# encoder_breakout.net
KiCad netlist of a schematic drawn in EAGLE
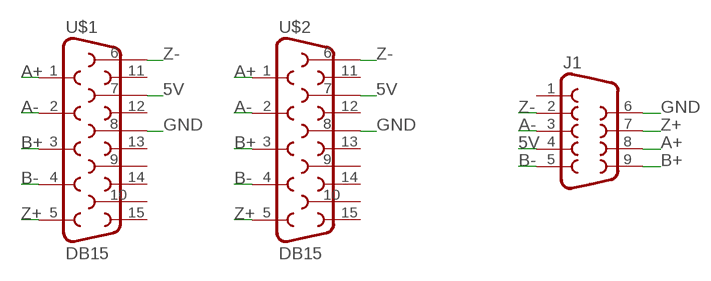
[diagram p0: schematic, sheet 1]

(export (version "E")
  (design (tool "Eeschema 10.0.6"))
  (components
    (comp (ref "J1")
      (value "DB9FEMALE")
      (footprint "eagle-import:DB9")
      (libsource (lib "eagle-import") (part "DB9FEMALE"))
    )
    (comp (ref "U$1")
      (value "DB15")
      (footprint "eagle-import:DB15")
      (libsource (lib "eagle-import") (part "DB15"))
    )
    (comp (ref "U$2")
      (value "DB15")
      (footprint "eagle-import:DB15")
      (libsource (lib "eagle-import") (part "DB15"))
    )
  )
  (nets
    (net (code "1") (name "/5V") (class "Default")
      (node (ref "J1") (pin "4") (pinfunction "4_4") (pintype "passive"))
      (node (ref "U$1") (pin "7") (pinfunction "7_7") (pintype "passive"))
      (node (ref "U$2") (pin "7") (pinfunction "7_7") (pintype "passive"))
    )
    (net (code "2") (name "/A+") (class "Default")
      (node (ref "J1") (pin "8") (pinfunction "8_8") (pintype "passive"))
      (node (ref "U$1") (pin "1") (pinfunction "1_1") (pintype "passive"))
      (node (ref "U$2") (pin "1") (pinfunction "1_1") (pintype "passive"))
    )
    (net (code "3") (name "/A-") (class "Default")
      (node (ref "J1") (pin "3") (pinfunction "3_3") (pintype "passive"))
      (node (ref "U$1") (pin "2") (pinfunction "2_2") (pintype "passive"))
      (node (ref "U$2") (pin "2") (pinfunction "2_2") (pintype "passive"))
    )
    (net (code "4") (name "/B+") (class "Default")
      (node (ref "J1") (pin "9") (pinfunction "9_9") (pintype "passive"))
      (node (ref "U$1") (pin "3") (pinfunction "3_3") (pintype "passive"))
      (node (ref "U$2") (pin "3") (pinfunction "3_3") (pintype "passive"))
    )
    (net (code "5") (name "/B-") (class "Default")
      (node (ref "J1") (pin "5") (pinfunction "5_5") (pintype "passive"))
      (node (ref "U$1") (pin "4") (pinfunction "4_4") (pintype "passive"))
      (node (ref "U$2") (pin "4") (pinfunction "4_4") (pintype "passive"))
    )
    (net (code "6") (name "/GND") (class "Default")
      (node (ref "J1") (pin "6") (pinfunction "6_6") (pintype "passive"))
      (node (ref "U$1") (pin "8") (pinfunction "8_8") (pintype "passive"))
      (node (ref "U$2") (pin "8") (pinfunction "8_8") (pintype "passive"))
    )
    (net (code "7") (name "/Z+") (class "Default")
      (node (ref "J1") (pin "7") (pinfunction "7_7") (pintype "passive"))
      (node (ref "U$1") (pin "5") (pinfunction "5_5") (pintype "passive"))
      (node (ref "U$2") (pin "5") (pinfunction "5_5") (pintype "passive"))
    )
    (net (code "8") (name "/Z-") (class "Default")
      (node (ref "J1") (pin "2") (pinfunction "2_2") (pintype "passive"))
      (node (ref "U$1") (pin "6") (pinfunction "6_6") (pintype "passive"))
      (node (ref "U$2") (pin "6") (pinfunction "6_6") (pintype "passive"))
    )
    (net (code "9") (name "unconnected-(J1-Pad1)") (class "Default")
      (node (ref "J1") (pin "1") (pinfunction "1_1") (pintype "passive"))
    )
    (net (code "10") (name "unconnected-(U$1-Pad9)") (class "Default")
      (node (ref "U$1") (pin "9") (pinfunction "9_9") (pintype "passive"))
    )
    (net (code "11") (name "unconnected-(U$1-Pad10)") (class "Default")
      (node (ref "U$1") (pin "10") (pinfunction "10_10") (pintype "passive"))
    )
    (net (code "12") (name "unconnected-(U$1-Pad11)") (class "Default")
      (node (ref "U$1") (pin "11") (pinfunction "11_11") (pintype "passive"))
    )
    (net (code "13") (name "unconnected-(U$1-Pad12)") (class "Default")
      (node (ref "U$1") (pin "12") (pinfunction "12_12") (pintype "passive"))
    )
    (net (code "14") (name "unconnected-(U$1-Pad13)") (class "Default")
      (node (ref "U$1") (pin "13") (pinfunction "13_13") (pintype "passive"))
    )
    (net (code "15") (name "unconnected-(U$1-Pad14)") (class "Default")
      (node (ref "U$1") (pin "14") (pinfunction "14_14") (pintype "passive"))
    )
    (net (code "16") (name "unconnected-(U$1-Pad15)") (class "Default")
      (node (ref "U$1") (pin "15") (pinfunction "15_15") (pintype "passive"))
    )
    (net (code "17") (name "unconnected-(U$2-Pad9)") (class "Default")
      (node (ref "U$2") (pin "9") (pinfunction "9_9") (pintype "passive"))
    )
    (net (code "18") (name "unconnected-(U$2-Pad10)") (class "Default")
      (node (ref "U$2") (pin "10") (pinfunction "10_10") (pintype "passive"))
    )
    (net (code "19") (name "unconnected-(U$2-Pad11)") (class "Default")
      (node (ref "U$2") (pin "11") (pinfunction "11_11") (pintype "passive"))
    )
    (net (code "20") (name "unconnected-(U$2-Pad12)") (class "Default")
      (node (ref "U$2") (pin "12") (pinfunction "12_12") (pintype "passive"))
    )
    (net (code "21") (name "unconnected-(U$2-Pad13)") (class "Default")
      (node (ref "U$2") (pin "13") (pinfunction "13_13") (pintype "passive"))
    )
    (net (code "22") (name "unconnected-(U$2-Pad14)") (class "Default")
      (node (ref "U$2") (pin "14") (pinfunction "14_14") (pintype "passive"))
    )
    (net (code "23") (name "unconnected-(U$2-Pad15)") (class "Default")
      (node (ref "U$2") (pin "15") (pinfunction "15_15") (pintype "passive"))
    )
  )
)
